# PC_module.net
KiCad netlist of a schematic drawn in Altium Designer
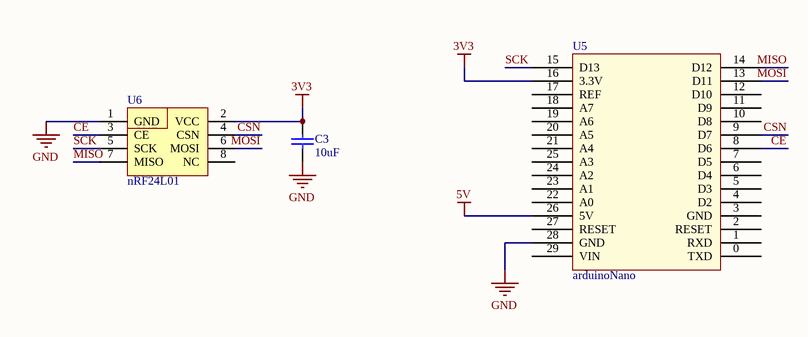
[diagram p0: PC_module.SchDoc]

(export (version "E")
  (design (tool "Eeschema 10.0.6"))
  (components
    (comp (ref "C3")
      (value "10uF")
      (footprint "RAD-0.3")
      (description "Capacitor")
      (fields (field (name "PUBLISHER") "Altium Limited"))
      (libsource (lib "Miscellaneous Devices") (part "Cap"))
    )
    (comp (ref "U5")
      (value "arduinoNano")
      (footprint "Arduino nano")
      (libsource (lib "skeemitehnika_lib") (part "arduinoNano"))
    )
    (comp (ref "U6") (value "nRF24L01") (libsource (lib "skeemitehnika_lib") (part "nRF24L01")))
  )
  (nets
    (net (code "1") (name "/CE") (class "Default")
      (node (ref "U5") (pin "8") (pinfunction "D6_8") (pintype "passive"))
      (node (ref "U6") (pin "3") (pinfunction "CE_3") (pintype "passive"))
    )
    (net (code "2") (name "/CSN") (class "Default")
      (node (ref "U5") (pin "9") (pinfunction "D7_9") (pintype "passive"))
      (node (ref "U6") (pin "4") (pinfunction "CSN_4") (pintype "passive"))
    )
    (net (code "3") (name "/MISO") (class "Default")
      (node (ref "U5") (pin "14") (pinfunction "D12_14") (pintype "passive"))
      (node (ref "U6") (pin "7") (pinfunction "MISO_7") (pintype "passive"))
    )
    (net (code "4") (name "/MOSI") (class "Default")
      (node (ref "U5") (pin "13") (pinfunction "D11_13") (pintype "passive"))
      (node (ref "U6") (pin "6") (pinfunction "MOSI_6") (pintype "passive"))
    )
    (net (code "5") (name "/SCK") (class "Default")
      (node (ref "U5") (pin "15") (pinfunction "D13_15") (pintype "passive"))
      (node (ref "U6") (pin "5") (pinfunction "SCK_5") (pintype "passive"))
    )
    (net (code "6") (name "3V3") (class "Default")
      (node (ref "C3") (pin "1") (pinfunction "1_1") (pintype "passive"))
      (node (ref "U5") (pin "16") (pinfunction "3.3V_16") (pintype "passive"))
      (node (ref "U6") (pin "2") (pinfunction "VCC_2") (pintype "passive"))
    )
    (net (code "7") (name "5V") (class "Default")
      (node (ref "U5") (pin "26") (pinfunction "5V_26") (pintype "passive"))
    )
    (net (code "8") (name "GND") (class "Default")
      (node (ref "C3") (pin "2") (pinfunction "2_2") (pintype "passive"))
      (node (ref "U5") (pin "28") (pinfunction "GND_28") (pintype "passive"))
      (node (ref "U6") (pin "1") (pinfunction "GND_1") (pintype "passive"))
    )
    (net (code "9") (name "unconnected-(U5-A0-Pad22)") (class "Default")
      (node (ref "U5") (pin "22") (pinfunction "A0_22") (pintype "passive"))
    )
    (net (code "10") (name "unconnected-(U5-A1-Pad23)") (class "Default")
      (node (ref "U5") (pin "23") (pinfunction "A1_23") (pintype "passive"))
    )
    (net (code "11") (name "unconnected-(U5-A2-Pad24)") (class "Default")
      (node (ref "U5") (pin "24") (pinfunction "A2_24") (pintype "passive"))
    )
    (net (code "12") (name "unconnected-(U5-A3-Pad25)") (class "Default")
      (node (ref "U5") (pin "25") (pinfunction "A3_25") (pintype "passive"))
    )
    (net (code "13") (name "unconnected-(U5-A4-Pad21)") (class "Default")
      (node (ref "U5") (pin "21") (pinfunction "A4_21") (pintype "passive"))
    )
    (net (code "14") (name "unconnected-(U5-A5-Pad20)") (class "Default")
      (node (ref "U5") (pin "20") (pinfunction "A5_20") (pintype "passive"))
    )
    (net (code "15") (name "unconnected-(U5-A6-Pad19)") (class "Default")
      (node (ref "U5") (pin "19") (pinfunction "A6_19") (pintype "passive"))
    )
    (net (code "16") (name "unconnected-(U5-A7-Pad18)") (class "Default")
      (node (ref "U5") (pin "18") (pinfunction "A7_18") (pintype "passive"))
    )
    (net (code "17") (name "unconnected-(U5-D2-Pad4)") (class "Default")
      (node (ref "U5") (pin "4") (pinfunction "D2_4") (pintype "passive"))
    )
    (net (code "18") (name "unconnected-(U5-D3-Pad5)") (class "Default")
      (node (ref "U5") (pin "5") (pinfunction "D3_5") (pintype "passive"))
    )
    (net (code "19") (name "unconnected-(U5-D4-Pad6)") (class "Default")
      (node (ref "U5") (pin "6") (pinfunction "D4_6") (pintype "passive"))
    )
    (net (code "20") (name "unconnected-(U5-D5-Pad7)") (class "Default")
      (node (ref "U5") (pin "7") (pinfunction "D5_7") (pintype "passive"))
    )
    (net (code "21") (name "unconnected-(U5-D8-Pad10)") (class "Default")
      (node (ref "U5") (pin "10") (pinfunction "D8_10") (pintype "passive"))
    )
    (net (code "22") (name "unconnected-(U5-D9-Pad11)") (class "Default")
      (node (ref "U5") (pin "11") (pinfunction "D9_11") (pintype "passive"))
    )
    (net (code "23") (name "unconnected-(U5-D10-Pad12)") (class "Default")
      (node (ref "U5") (pin "12") (pinfunction "D10_12") (pintype "passive"))
    )
    (net (code "24") (name "unconnected-(U5-GND-Pad3)") (class "Default")
      (node (ref "U5") (pin "3") (pinfunction "GND_3") (pintype "passive"))
    )
    (net (code "25") (name "unconnected-(U5-REF-Pad17)") (class "Default")
      (node (ref "U5") (pin "17") (pinfunction "REF_17") (pintype "passive"))
    )
    (net (code "26") (name "unconnected-(U5-RESET-Pad2)") (class "Default")
      (node (ref "U5") (pin "2") (pinfunction "RESET_2") (pintype "passive"))
    )
    (net (code "27") (name "unconnected-(U5-RESET-Pad27)") (class "Default")
      (node (ref "U5") (pin "27") (pinfunction "RESET_27") (pintype "passive"))
    )
    (net (code "28") (name "unconnected-(U5-RXD-Pad1)") (class "Default")
      (node (ref "U5") (pin "1") (pinfunction "RXD_1") (pintype "passive"))
    )
    (net (code "29") (name "unconnected-(U5-TXD-Pad0)") (class "Default")
      (node (ref "U5") (pin "0") (pinfunction "TXD_0") (pintype "passive"))
    )
    (net (code "30") (name "unconnected-(U5-VIN-Pad29)") (class "Default")
      (node (ref "U5") (pin "29") (pinfunction "VIN_29") (pintype "passive"))
    )
    (net (code "31") (name "unconnected-(U6-NC-Pad8)") (class "Default")
      (node (ref "U6") (pin "8") (pinfunction "NC_8") (pintype "passive"))
    )
  )
)
